# Relay.net
KiCad netlist of a schematic drawn in Altium Designer
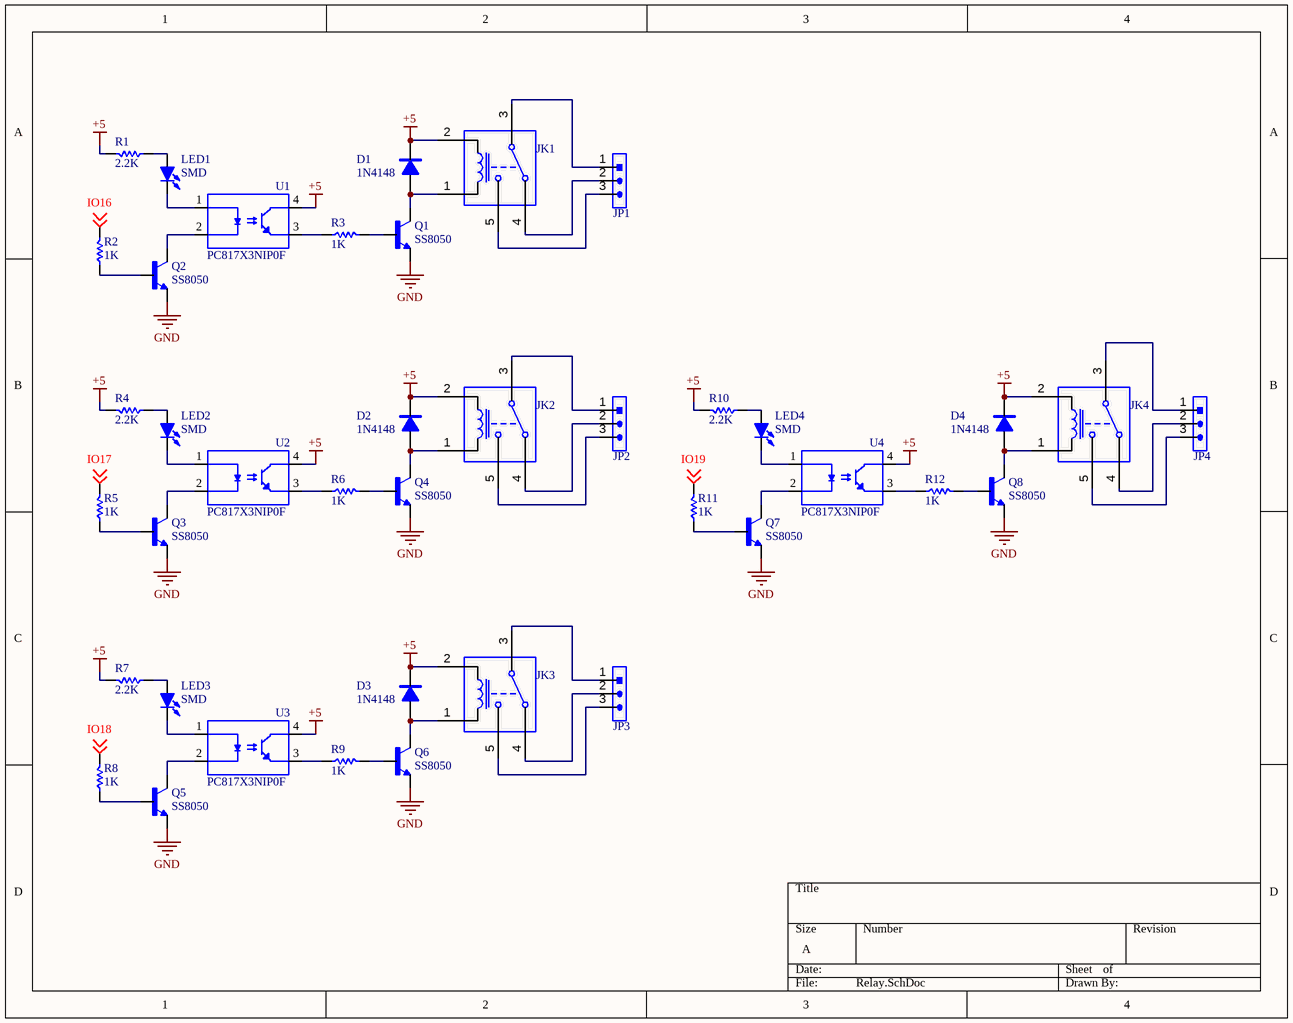
[diagram p0: Relay.SchDoc]

(export (version "E")
  (design (tool "Eeschema 10.0.6"))
  (components
    (comp (ref "D1")
      (value "1N4148")
      (footprint "MINI_MELF (LL34)")
      (description "High speed switching diode")
      (fields (field (name "版权归属") "源创客"))
      (libsource (lib "Diode-Zener-Rectifier Bridge") (part "1N4148"))
    )
    (comp (ref "D2")
      (value "1N4148")
      (footprint "MINI_MELF (LL34)")
      (description "High speed switching diode")
      (fields (field (name "版权归属") "源创客"))
      (libsource (lib "Diode-Zener-Rectifier Bridge") (part "1N4148"))
    )
    (comp (ref "D3")
      (value "1N4148")
      (footprint "MINI_MELF (LL34)")
      (description "High speed switching diode")
      (fields (field (name "版权归属") "源创客"))
      (libsource (lib "Diode-Zener-Rectifier Bridge") (part "1N4148"))
    )
    (comp (ref "D4")
      (value "1N4148")
      (footprint "MINI_MELF (LL34)")
      (description "High speed switching diode")
      (fields (field (name "版权归属") "源创客"))
      (libsource (lib "Diode-Zener-Rectifier Bridge") (part "1N4148"))
    )
    (comp (ref "JK1")
      (value "SRD-05VDC-SL-C")
      (footprint "SRD-C_B")
      (description "5V单路双控继电器")
      (fields (field (name "版权归属") "源创客"))
      (libsource (lib "Relay") (part "SRD-05VDC-SL-C"))
    )
    (comp (ref "JK2")
      (value "SRD-05VDC-SL-C")
      (footprint "SRD-C_B")
      (description "5V单路双控继电器")
      (fields (field (name "版权归属") "源创客"))
      (libsource (lib "Relay") (part "SRD-05VDC-SL-C"))
    )
    (comp (ref "JK3")
      (value "SRD-05VDC-SL-C")
      (footprint "SRD-C_B")
      (description "5V单路双控继电器")
      (fields (field (name "版权归属") "源创客"))
      (libsource (lib "Relay") (part "SRD-05VDC-SL-C"))
    )
    (comp (ref "JK4")
      (value "SRD-05VDC-SL-C")
      (footprint "SRD-C_B")
      (description "5V单路双控继电器")
      (fields (field (name "版权归属") "源创客"))
      (libsource (lib "Relay") (part "SRD-05VDC-SL-C"))
    )
    (comp (ref "JP1")
      (value "HDR-1X3")
      (footprint "KF301-3P")
      (description "3P Connector")
      (fields (field (name "版权归属") "源创客"))
      (libsource (lib "Connectors") (part "Header 3"))
    )
    (comp (ref "JP2")
      (value "HDR-1X3")
      (footprint "KF301-3P")
      (description "3P Connector")
      (fields (field (name "版权归属") "源创客"))
      (libsource (lib "Connectors") (part "Header 3"))
    )
    (comp (ref "JP3")
      (value "HDR-1X3")
      (footprint "KF301-3P")
      (description "3P Connector")
      (fields (field (name "版权归属") "源创客"))
      (libsource (lib "Connectors") (part "Header 3"))
    )
    (comp (ref "JP4")
      (value "HDR-1X3")
      (footprint "KF301-3P")
      (description "3P Connector")
      (fields (field (name "版权归属") "源创客"))
      (libsource (lib "Connectors") (part "Header 3"))
    )
    (comp (ref "LED1")
      (value "SMD")
      (footprint "LED 0805B")
      (description "Blue LED")
      (fields (field (name "版权归属") "源创客"))
      (libsource (lib "LED") (part "LED-SMD"))
    )
    (comp (ref "LED2")
      (value "SMD")
      (footprint "LED 0805B")
      (description "Blue LED")
      (fields (field (name "版权归属") "源创客"))
      (libsource (lib "LED") (part "LED-SMD"))
    )
    (comp (ref "LED3")
      (value "SMD")
      (footprint "LED 0805B")
      (description "Blue LED")
      (fields (field (name "版权归属") "源创客"))
      (libsource (lib "LED") (part "LED-SMD"))
    )
    (comp (ref "LED4")
      (value "SMD")
      (footprint "LED 0805B")
      (description "Blue LED")
      (fields (field (name "版权归属") "源创客"))
      (libsource (lib "LED") (part "LED-SMD"))
    )
    (comp (ref "Q1")
      (value "SS8050")
      (footprint "SOT23-BEC")
      (description "Bipolar _BJT_ Transistor NPN General Purpose Amplifier Surface Mount")
      (fields (field (name "MF") "ON Semiconductor") (field (name "MP") "BCW31"))
      (libsource (lib "BCW31_") (part "BCW31*"))
    )
    (comp (ref "Q2")
      (value "SS8050")
      (footprint "SOT23-BEC")
      (description "Bipolar _BJT_ Transistor NPN General Purpose Amplifier Surface Mount")
      (fields (field (name "MF") "ON Semiconductor") (field (name "MP") "BCW31"))
      (libsource (lib "BCW31_") (part "BCW31*"))
    )
    (comp (ref "Q3")
      (value "SS8050")
      (footprint "SOT23-BEC")
      (description "Bipolar _BJT_ Transistor NPN General Purpose Amplifier Surface Mount")
      (fields (field (name "MF") "ON Semiconductor") (field (name "MP") "BCW31"))
      (libsource (lib "BCW31_") (part "BCW31*"))
    )
    (comp (ref "Q4")
      (value "SS8050")
      (footprint "SOT23-BEC")
      (description "Bipolar _BJT_ Transistor NPN General Purpose Amplifier Surface Mount")
      (fields (field (name "MF") "ON Semiconductor") (field (name "MP") "BCW31"))
      (libsource (lib "BCW31_") (part "BCW31*"))
    )
    (comp (ref "Q5")
      (value "SS8050")
      (footprint "SOT23-BEC")
      (description "Bipolar _BJT_ Transistor NPN General Purpose Amplifier Surface Mount")
      (fields (field (name "MF") "ON Semiconductor") (field (name "MP") "BCW31"))
      (libsource (lib "BCW31_") (part "BCW31*"))
    )
    (comp (ref "Q6")
      (value "SS8050")
      (footprint "SOT23-BEC")
      (description "Bipolar _BJT_ Transistor NPN General Purpose Amplifier Surface Mount")
      (fields (field (name "MF") "ON Semiconductor") (field (name "MP") "BCW31"))
      (libsource (lib "BCW31_") (part "BCW31*"))
    )
    (comp (ref "Q7")
      (value "SS8050")
      (footprint "SOT23-BEC")
      (description "Bipolar _BJT_ Transistor NPN General Purpose Amplifier Surface Mount")
      (fields (field (name "MF") "ON Semiconductor") (field (name "MP") "BCW31"))
      (libsource (lib "BCW31_") (part "BCW31*"))
    )
    (comp (ref "Q8")
      (value "SS8050")
      (footprint "SOT23-BEC")
      (description "Bipolar _BJT_ Transistor NPN General Purpose Amplifier Surface Mount")
      (fields (field (name "MF") "ON Semiconductor") (field (name "MP") "BCW31"))
      (libsource (lib "BCW31_") (part "BCW31*"))
    )
    (comp (ref "R1")
      (value "2.2K")
      (footprint "R 0805")
      (description "Chip resistor")
      (fields (field (name "版权归属") "源创客"))
      (libsource (lib "Passive (Resistor-Capacitor-Inductor-Veristor-Ferrite)") (part "R"))
    )
    (comp (ref "R2")
      (value "1K")
      (footprint "R 0805")
      (description "Chip resistor")
      (fields (field (name "版权归属") "源创客"))
      (libsource (lib "Passive (Resistor-Capacitor-Inductor-Veristor-Ferrite)") (part "R"))
    )
    (comp (ref "R3")
      (value "1K")
      (footprint "R 0805")
      (description "Chip resistor")
      (fields (field (name "版权归属") "源创客"))
      (libsource (lib "Passive (Resistor-Capacitor-Inductor-Veristor-Ferrite)") (part "R"))
    )
    (comp (ref "R4")
      (value "2.2K")
      (footprint "R 0805")
      (description "Chip resistor")
      (fields (field (name "版权归属") "源创客"))
      (libsource (lib "Passive (Resistor-Capacitor-Inductor-Veristor-Ferrite)") (part "R"))
    )
    (comp (ref "R5")
      (value "1K")
      (footprint "R 0805")
      (description "Chip resistor")
      (fields (field (name "版权归属") "源创客"))
      (libsource (lib "Passive (Resistor-Capacitor-Inductor-Veristor-Ferrite)") (part "R"))
    )
    (comp (ref "R6")
      (value "1K")
      (footprint "R 0805")
      (description "Chip resistor")
      (fields (field (name "版权归属") "源创客"))
      (libsource (lib "Passive (Resistor-Capacitor-Inductor-Veristor-Ferrite)") (part "R"))
    )
    (comp (ref "R7")
      (value "2.2K")
      (footprint "R 0805")
      (description "Chip resistor")
      (fields (field (name "版权归属") "源创客"))
      (libsource (lib "Passive (Resistor-Capacitor-Inductor-Veristor-Ferrite)") (part "R"))
    )
    (comp (ref "R8")
      (value "1K")
      (footprint "R 0805")
      (description "Chip resistor")
      (fields (field (name "版权归属") "源创客"))
      (libsource (lib "Passive (Resistor-Capacitor-Inductor-Veristor-Ferrite)") (part "R"))
    )
    (comp (ref "R9")
      (value "1K")
      (footprint "R 0805")
      (description "Chip resistor")
      (fields (field (name "版权归属") "源创客"))
      (libsource (lib "Passive (Resistor-Capacitor-Inductor-Veristor-Ferrite)") (part "R"))
    )
    (comp (ref "R10")
      (value "2.2K")
      (footprint "R 0805")
      (description "Chip resistor")
      (fields (field (name "版权归属") "源创客"))
      (libsource (lib "Passive (Resistor-Capacitor-Inductor-Veristor-Ferrite)") (part "R"))
    )
    (comp (ref "R11")
      (value "1K")
      (footprint "R 0805")
      (description "Chip resistor")
      (fields (field (name "版权归属") "源创客"))
      (libsource (lib "Passive (Resistor-Capacitor-Inductor-Veristor-Ferrite)") (part "R"))
    )
    (comp (ref "R12")
      (value "1K")
      (footprint "R 0805")
      (description "Chip resistor")
      (fields (field (name "版权归属") "源创客"))
      (libsource (lib "Passive (Resistor-Capacitor-Inductor-Veristor-Ferrite)") (part "R"))
    )
    (comp (ref "U1")
      (value "PC817X3NIP0F")
      (footprint "SOIC254P1000X400-4N")
      (description "Optoisolator Transistor Output 5000Vrms 1 Channel 4-SMD")
      (fields (field (name "MF") "SHARP/Socle Technology"))
      (libsource (lib "PC817X3NIP0F") (part "PC817X3NIP0F"))
    )
    (comp (ref "U2")
      (value "PC817X3NIP0F")
      (footprint "SOIC254P1000X400-4N")
      (description "Optoisolator Transistor Output 5000Vrms 1 Channel 4-SMD")
      (fields (field (name "MF") "SHARP/Socle Technology"))
      (libsource (lib "PC817X3NIP0F") (part "PC817X3NIP0F"))
    )
    (comp (ref "U3")
      (value "PC817X3NIP0F")
      (footprint "SOIC254P1000X400-4N")
      (description "Optoisolator Transistor Output 5000Vrms 1 Channel 4-SMD")
      (fields (field (name "MF") "SHARP/Socle Technology"))
      (libsource (lib "PC817X3NIP0F") (part "PC817X3NIP0F"))
    )
    (comp (ref "U4")
      (value "PC817X3NIP0F")
      (footprint "SOIC254P1000X400-4N")
      (description "Optoisolator Transistor Output 5000Vrms 1 Channel 4-SMD")
      (fields (field (name "MF") "SHARP/Socle Technology"))
      (libsource (lib "PC817X3NIP0F") (part "PC817X3NIP0F"))
    )
  )
  (nets
    (net (code "1") (name "+5") (class "Default")
      (node (ref "D1") (pin "2") (pinfunction "K_2") (pintype "passive"))
      (node (ref "D2") (pin "2") (pinfunction "K_2") (pintype "passive"))
      (node (ref "D3") (pin "2") (pinfunction "K_2") (pintype "passive"))
      (node (ref "D4") (pin "2") (pinfunction "K_2") (pintype "passive"))
      (node (ref "JK1") (pin "2") (pinfunction "Coil_2_2") (pintype "passive"))
      (node (ref "JK2") (pin "2") (pinfunction "Coil_2_2") (pintype "passive"))
      (node (ref "JK3") (pin "2") (pinfunction "Coil_2_2") (pintype "passive"))
      (node (ref "JK4") (pin "2") (pinfunction "Coil_2_2") (pintype "passive"))
      (node (ref "R1") (pin "2") (pinfunction "2_2") (pintype "passive"))
      (node (ref "R10") (pin "2") (pinfunction "2_2") (pintype "passive"))
      (node (ref "R4") (pin "2") (pinfunction "2_2") (pintype "passive"))
      (node (ref "R7") (pin "2") (pinfunction "2_2") (pintype "passive"))
      (node (ref "U1") (pin "4") (pinfunction "COLLECTOR_4") (pintype "passive"))
      (node (ref "U2") (pin "4") (pinfunction "COLLECTOR_4") (pintype "passive"))
      (node (ref "U3") (pin "4") (pinfunction "COLLECTOR_4") (pintype "passive"))
      (node (ref "U4") (pin "4") (pinfunction "COLLECTOR_4") (pintype "passive"))
    )
    (net (code "2") (name "GND") (class "Default")
      (node (ref "Q1") (pin "E") (pinfunction "E_E") (pintype "passive"))
      (node (ref "Q2") (pin "E") (pinfunction "E_E") (pintype "passive"))
      (node (ref "Q3") (pin "E") (pinfunction "E_E") (pintype "passive"))
      (node (ref "Q4") (pin "E") (pinfunction "E_E") (pintype "passive"))
      (node (ref "Q5") (pin "E") (pinfunction "E_E") (pintype "passive"))
      (node (ref "Q6") (pin "E") (pinfunction "E_E") (pintype "passive"))
      (node (ref "Q7") (pin "E") (pinfunction "E_E") (pintype "passive"))
      (node (ref "Q8") (pin "E") (pinfunction "E_E") (pintype "passive"))
    )
    (net (code "3") (name "IO16") (class "Default")
      (node (ref "R2") (pin "2") (pinfunction "2_2") (pintype "passive"))
    )
    (net (code "4") (name "IO17") (class "Default")
      (node (ref "R5") (pin "2") (pinfunction "2_2") (pintype "passive"))
    )
    (net (code "5") (name "IO18") (class "Default")
      (node (ref "R8") (pin "2") (pinfunction "2_2") (pintype "passive"))
    )
    (net (code "6") (name "IO19") (class "Default")
      (node (ref "R11") (pin "2") (pinfunction "2_2") (pintype "passive"))
    )
    (net (code "7") (name "Net-(D1-A)") (class "Default")
      (node (ref "D1") (pin "1") (pinfunction "A_1") (pintype "passive"))
      (node (ref "JK1") (pin "1") (pinfunction "Coil_1_1") (pintype "passive"))
      (node (ref "Q1") (pin "C") (pinfunction "C_C") (pintype "passive"))
    )
    (net (code "8") (name "Net-(D2-A)") (class "Default")
      (node (ref "D2") (pin "1") (pinfunction "A_1") (pintype "passive"))
      (node (ref "JK2") (pin "1") (pinfunction "Coil_1_1") (pintype "passive"))
      (node (ref "Q4") (pin "C") (pinfunction "C_C") (pintype "passive"))
    )
    (net (code "9") (name "Net-(D3-A)") (class "Default")
      (node (ref "D3") (pin "1") (pinfunction "A_1") (pintype "passive"))
      (node (ref "JK3") (pin "1") (pinfunction "Coil_1_1") (pintype "passive"))
      (node (ref "Q6") (pin "C") (pinfunction "C_C") (pintype "passive"))
    )
    (net (code "10") (name "Net-(D4-A)") (class "Default")
      (node (ref "D4") (pin "1") (pinfunction "A_1") (pintype "passive"))
      (node (ref "JK4") (pin "1") (pinfunction "Coil_1_1") (pintype "passive"))
      (node (ref "Q8") (pin "C") (pinfunction "C_C") (pintype "passive"))
    )
    (net (code "11") (name "Net-(JK1-Pad3)") (class "Default")
      (node (ref "JK1") (pin "3") (pinfunction "3_3") (pintype "passive"))
      (node (ref "JP1") (pin "1") (pintype "passive"))
    )
    (net (code "12") (name "Net-(JK1-Pad4)") (class "Default")
      (node (ref "JK1") (pin "4") (pinfunction "4_4") (pintype "passive"))
      (node (ref "JP1") (pin "2") (pintype "passive"))
    )
    (net (code "13") (name "Net-(JK1-Pad5)") (class "Default")
      (node (ref "JK1") (pin "5") (pinfunction "5_5") (pintype "passive"))
      (node (ref "JP1") (pin "3") (pintype "passive"))
    )
    (net (code "14") (name "Net-(JK2-Pad3)") (class "Default")
      (node (ref "JK2") (pin "3") (pinfunction "3_3") (pintype "passive"))
      (node (ref "JP2") (pin "1") (pintype "passive"))
    )
    (net (code "15") (name "Net-(JK2-Pad4)") (class "Default")
      (node (ref "JK2") (pin "4") (pinfunction "4_4") (pintype "passive"))
      (node (ref "JP2") (pin "2") (pintype "passive"))
    )
    (net (code "16") (name "Net-(JK2-Pad5)") (class "Default")
      (node (ref "JK2") (pin "5") (pinfunction "5_5") (pintype "passive"))
      (node (ref "JP2") (pin "3") (pintype "passive"))
    )
    (net (code "17") (name "Net-(JK3-Pad3)") (class "Default")
      (node (ref "JK3") (pin "3") (pinfunction "3_3") (pintype "passive"))
      (node (ref "JP3") (pin "1") (pintype "passive"))
    )
    (net (code "18") (name "Net-(JK3-Pad4)") (class "Default")
      (node (ref "JK3") (pin "4") (pinfunction "4_4") (pintype "passive"))
      (node (ref "JP3") (pin "2") (pintype "passive"))
    )
    (net (code "19") (name "Net-(JK3-Pad5)") (class "Default")
      (node (ref "JK3") (pin "5") (pinfunction "5_5") (pintype "passive"))
      (node (ref "JP3") (pin "3") (pintype "passive"))
    )
    (net (code "20") (name "Net-(JK4-Pad3)") (class "Default")
      (node (ref "JK4") (pin "3") (pinfunction "3_3") (pintype "passive"))
      (node (ref "JP4") (pin "1") (pintype "passive"))
    )
    (net (code "21") (name "Net-(JK4-Pad4)") (class "Default")
      (node (ref "JK4") (pin "4") (pinfunction "4_4") (pintype "passive"))
      (node (ref "JP4") (pin "2") (pintype "passive"))
    )
    (net (code "22") (name "Net-(JK4-Pad5)") (class "Default")
      (node (ref "JK4") (pin "5") (pinfunction "5_5") (pintype "passive"))
      (node (ref "JP4") (pin "3") (pintype "passive"))
    )
    (net (code "23") (name "Net-(LED1-A)") (class "Default")
      (node (ref "LED1") (pin "1") (pinfunction "A_1") (pintype "passive"))
      (node (ref "R1") (pin "1") (pinfunction "1_1") (pintype "passive"))
    )
    (net (code "24") (name "Net-(LED1-K)") (class "Default")
      (node (ref "LED1") (pin "2") (pinfunction "K_2") (pintype "passive"))
      (node (ref "U1") (pin "1") (pinfunction "ANODE_1") (pintype "passive"))
    )
    (net (code "25") (name "Net-(LED2-A)") (class "Default")
      (node (ref "LED2") (pin "1") (pinfunction "A_1") (pintype "passive"))
      (node (ref "R4") (pin "1") (pinfunction "1_1") (pintype "passive"))
    )
    (net (code "26") (name "Net-(LED2-K)") (class "Default")
      (node (ref "LED2") (pin "2") (pinfunction "K_2") (pintype "passive"))
      (node (ref "U2") (pin "1") (pinfunction "ANODE_1") (pintype "passive"))
    )
    (net (code "27") (name "Net-(LED3-A)") (class "Default")
      (node (ref "LED3") (pin "1") (pinfunction "A_1") (pintype "passive"))
      (node (ref "R7") (pin "1") (pinfunction "1_1") (pintype "passive"))
    )
    (net (code "28") (name "Net-(LED3-K)") (class "Default")
      (node (ref "LED3") (pin "2") (pinfunction "K_2") (pintype "passive"))
      (node (ref "U3") (pin "1") (pinfunction "ANODE_1") (pintype "passive"))
    )
    (net (code "29") (name "Net-(LED4-A)") (class "Default")
      (node (ref "LED4") (pin "1") (pinfunction "A_1") (pintype "passive"))
      (node (ref "R10") (pin "1") (pinfunction "1_1") (pintype "passive"))
    )
    (net (code "30") (name "Net-(LED4-K)") (class "Default")
      (node (ref "LED4") (pin "2") (pinfunction "K_2") (pintype "passive"))
      (node (ref "U4") (pin "1") (pinfunction "ANODE_1") (pintype "passive"))
    )
    (net (code "31") (name "Net-(Q1-PadB)") (class "Default")
      (node (ref "Q1") (pin "B") (pinfunction "B_B") (pintype "passive"))
      (node (ref "R3") (pin "2") (pinfunction "2_2") (pintype "passive"))
    )
    (net (code "32") (name "Net-(Q2-PadB)") (class "Default")
      (node (ref "Q2") (pin "B") (pinfunction "B_B") (pintype "passive"))
      (node (ref "R2") (pin "1") (pinfunction "1_1") (pintype "passive"))
    )
    (net (code "33") (name "Net-(Q3-PadB)") (class "Default")
      (node (ref "Q3") (pin "B") (pinfunction "B_B") (pintype "passive"))
      (node (ref "R5") (pin "1") (pinfunction "1_1") (pintype "passive"))
    )
    (net (code "34") (name "Net-(Q4-PadB)") (class "Default")
      (node (ref "Q4") (pin "B") (pinfunction "B_B") (pintype "passive"))
      (node (ref "R6") (pin "2") (pinfunction "2_2") (pintype "passive"))
    )
    (net (code "35") (name "Net-(Q5-PadB)") (class "Default")
      (node (ref "Q5") (pin "B") (pinfunction "B_B") (pintype "passive"))
      (node (ref "R8") (pin "1") (pinfunction "1_1") (pintype "passive"))
    )
    (net (code "36") (name "Net-(Q6-PadB)") (class "Default")
      (node (ref "Q6") (pin "B") (pinfunction "B_B") (pintype "passive"))
      (node (ref "R9") (pin "2") (pinfunction "2_2") (pintype "passive"))
    )
    (net (code "37") (name "Net-(Q7-PadB)") (class "Default")
      (node (ref "Q7") (pin "B") (pinfunction "B_B") (pintype "passive"))
      (node (ref "R11") (pin "1") (pinfunction "1_1") (pintype "passive"))
    )
    (net (code "38") (name "Net-(Q8-PadB)") (class "Default")
      (node (ref "Q8") (pin "B") (pinfunction "B_B") (pintype "passive"))
      (node (ref "R12") (pin "2") (pinfunction "2_2") (pintype "passive"))
    )
    (net (code "39") (name "Net-(U1-CATHODE)") (class "Default")
      (node (ref "Q2") (pin "C") (pinfunction "C_C") (pintype "passive"))
      (node (ref "U1") (pin "2") (pinfunction "CATHODE_2") (pintype "passive"))
    )
    (net (code "40") (name "Net-(U1-EMITTER)") (class "Default")
      (node (ref "R3") (pin "1") (pinfunction "1_1") (pintype "passive"))
      (node (ref "U1") (pin "3") (pinfunction "EMITTER_3") (pintype "passive"))
    )
    (net (code "41") (name "Net-(U2-CATHODE)") (class "Default")
      (node (ref "Q3") (pin "C") (pinfunction "C_C") (pintype "passive"))
      (node (ref "U2") (pin "2") (pinfunction "CATHODE_2") (pintype "passive"))
    )
    (net (code "42") (name "Net-(U2-EMITTER)") (class "Default")
      (node (ref "R6") (pin "1") (pinfunction "1_1") (pintype "passive"))
      (node (ref "U2") (pin "3") (pinfunction "EMITTER_3") (pintype "passive"))
    )
    (net (code "43") (name "Net-(U3-CATHODE)") (class "Default")
      (node (ref "Q5") (pin "C") (pinfunction "C_C") (pintype "passive"))
      (node (ref "U3") (pin "2") (pinfunction "CATHODE_2") (pintype "passive"))
    )
    (net (code "44") (name "Net-(U3-EMITTER)") (class "Default")
      (node (ref "R9") (pin "1") (pinfunction "1_1") (pintype "passive"))
      (node (ref "U3") (pin "3") (pinfunction "EMITTER_3") (pintype "passive"))
    )
    (net (code "45") (name "Net-(U4-CATHODE)") (class "Default")
      (node (ref "Q7") (pin "C") (pinfunction "C_C") (pintype "passive"))
      (node (ref "U4") (pin "2") (pinfunction "CATHODE_2") (pintype "passive"))
    )
    (net (code "46") (name "Net-(U4-EMITTER)") (class "Default")
      (node (ref "R12") (pin "1") (pinfunction "1_1") (pintype "passive"))
      (node (ref "U4") (pin "3") (pinfunction "EMITTER_3") (pintype "passive"))
    )
  )
)
